# untitled.net
KiCad netlist of a schematic drawn in EAGLE
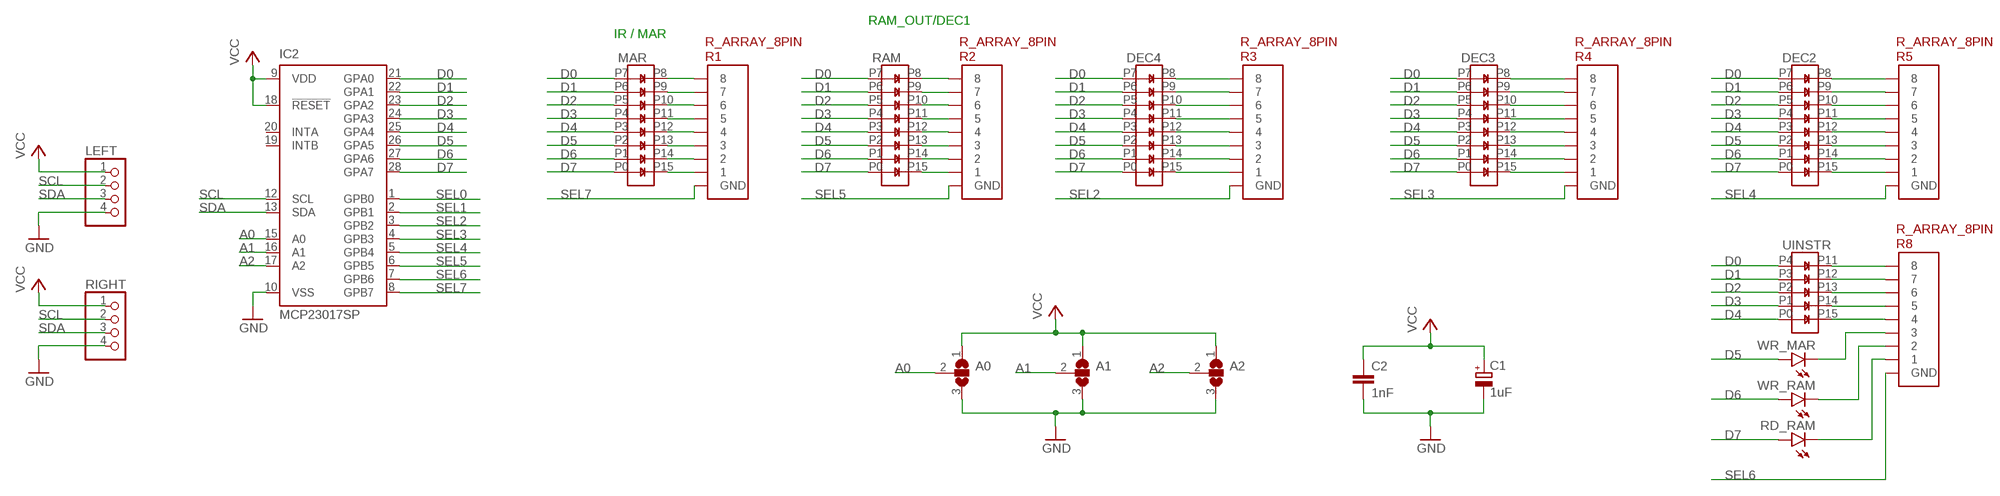
[diagram p0: schematic, sheet 1]

(export (version "E")
  (design (tool "Eeschema 10.0.6"))
  (components
    (comp (ref "A0")
      (value "SJ2W")
      (footprint "eagle-import:SJ_2")
      (libsource (lib "eagle-import") (part "SJ2W"))
    )
    (comp (ref "A1")
      (value "SJ2W")
      (footprint "eagle-import:SJ_2")
      (libsource (lib "eagle-import") (part "SJ2W"))
    )
    (comp (ref "A2")
      (value "SJ2W")
      (footprint "eagle-import:SJ_2")
      (libsource (lib "eagle-import") (part "SJ2W"))
    )
    (comp (ref "C1")
      (value "1uF")
      (footprint "eagle-import:E2,5-6")
      (libsource (lib "eagle-import") (part "CPOL-EUE2.5-6"))
    )
    (comp (ref "C2")
      (value "1nF")
      (footprint "eagle-import:C2.5-2")
      (libsource (lib "eagle-import") (part "C2.5/2"))
    )
    (comp (ref "DEC2")
      (value "LB8")
      (footprint "eagle-import:LB8")
      (libsource (lib "eagle-import") (part "LB8"))
    )
    (comp (ref "DEC3")
      (value "LB8")
      (footprint "eagle-import:LB8")
      (libsource (lib "eagle-import") (part "LB8"))
    )
    (comp (ref "DEC4")
      (value "LB8")
      (footprint "eagle-import:LB8")
      (libsource (lib "eagle-import") (part "LB8"))
    )
    (comp (ref "IC2")
      (value "MCP23017SP")
      (footprint "eagle-import:DIL28-3")
      (fields (field (name "MF") "MICROCHIP") (field (name "MPN") "MCP23017-E/SP"))
      (libsource (lib "eagle-import") (part "MCP23017SP"))
    )
    (comp (ref "LEFT")
      (value "PINHD-1X4")
      (footprint "eagle-import:1X04")
      (libsource (lib "eagle-import") (part "PINHD-1X4"))
    )
    (comp (ref "MAR")
      (value "LB8")
      (footprint "eagle-import:LB8")
      (libsource (lib "eagle-import") (part "LB8"))
    )
    (comp (ref "R1")
      (value "R_ARRAY_8PIN")
      (footprint "eagle-import:R_ARRAY_8PIN")
      (libsource (lib "eagle-import") (part "R_ARRAY_8PIN"))
    )
    (comp (ref "R2")
      (value "R_ARRAY_8PIN")
      (footprint "eagle-import:R_ARRAY_8PIN")
      (libsource (lib "eagle-import") (part "R_ARRAY_8PIN"))
    )
    (comp (ref "R3")
      (value "R_ARRAY_8PIN")
      (footprint "eagle-import:R_ARRAY_8PIN")
      (libsource (lib "eagle-import") (part "R_ARRAY_8PIN"))
    )
    (comp (ref "R4")
      (value "R_ARRAY_8PIN")
      (footprint "eagle-import:R_ARRAY_8PIN")
      (libsource (lib "eagle-import") (part "R_ARRAY_8PIN"))
    )
    (comp (ref "R5")
      (value "R_ARRAY_8PIN")
      (footprint "eagle-import:R_ARRAY_8PIN")
      (libsource (lib "eagle-import") (part "R_ARRAY_8PIN"))
    )
    (comp (ref "R8")
      (value "R_ARRAY_8PIN")
      (footprint "eagle-import:R_ARRAY_8PIN")
      (libsource (lib "eagle-import") (part "R_ARRAY_8PIN"))
    )
    (comp (ref "RAM")
      (value "LB8")
      (footprint "eagle-import:LB8")
      (libsource (lib "eagle-import") (part "LB8"))
    )
    (comp (ref "RD_RAM")
      (value "LED3MM")
      (footprint "eagle-import:LED3MM")
      (libsource (lib "eagle-import") (part "LED3MM"))
    )
    (comp (ref "RIGHT")
      (value "PINHD-1X4")
      (footprint "eagle-import:1X04")
      (libsource (lib "eagle-import") (part "PINHD-1X4"))
    )
    (comp (ref "UINSTR")
      (value "LB5")
      (footprint "eagle-import:LB5")
      (libsource (lib "eagle-import") (part "LB5"))
    )
    (comp (ref "WR_MAR")
      (value "LED3MM")
      (footprint "eagle-import:LED3MM")
      (libsource (lib "eagle-import") (part "LED3MM"))
    )
    (comp (ref "WR_RAM")
      (value "LED3MM")
      (footprint "eagle-import:LED3MM")
      (libsource (lib "eagle-import") (part "LED3MM"))
    )
  )
  (nets
    (net (code "1") (name "/A0") (class "Default")
      (node (ref "A0") (pin "2") (pinfunction "2_2") (pintype "passive"))
      (node (ref "IC2") (pin "15") (pinfunction "A0_15") (pintype "input"))
    )
    (net (code "2") (name "/A1") (class "Default")
      (node (ref "A1") (pin "2") (pinfunction "2_2") (pintype "passive"))
      (node (ref "IC2") (pin "16") (pinfunction "A1_16") (pintype "input"))
    )
    (net (code "3") (name "/A2") (class "Default")
      (node (ref "A2") (pin "2") (pinfunction "2_2") (pintype "passive"))
      (node (ref "IC2") (pin "17") (pinfunction "A2_17") (pintype "input"))
    )
    (net (code "4") (name "/D0") (class "Default")
      (node (ref "DEC2") (pin "P7") (pinfunction "P7_P7") (pintype "bidirectional"))
      (node (ref "DEC3") (pin "P7") (pinfunction "P7_P7") (pintype "bidirectional"))
      (node (ref "DEC4") (pin "P7") (pinfunction "P7_P7") (pintype "bidirectional"))
      (node (ref "IC2") (pin "21") (pinfunction "GPA0_21") (pintype "bidirectional"))
      (node (ref "MAR") (pin "P7") (pinfunction "P7_P7") (pintype "bidirectional"))
      (node (ref "RAM") (pin "P7") (pinfunction "P7_P7") (pintype "bidirectional"))
      (node (ref "UINSTR") (pin "P4") (pinfunction "P4_P4") (pintype "bidirectional"))
    )
    (net (code "5") (name "/D1") (class "Default")
      (node (ref "DEC2") (pin "P6") (pinfunction "P6_P6") (pintype "bidirectional"))
      (node (ref "DEC3") (pin "P6") (pinfunction "P6_P6") (pintype "bidirectional"))
      (node (ref "DEC4") (pin "P6") (pinfunction "P6_P6") (pintype "bidirectional"))
      (node (ref "IC2") (pin "22") (pinfunction "GPA1_22") (pintype "bidirectional"))
      (node (ref "MAR") (pin "P6") (pinfunction "P6_P6") (pintype "bidirectional"))
      (node (ref "RAM") (pin "P6") (pinfunction "P6_P6") (pintype "bidirectional"))
      (node (ref "UINSTR") (pin "P3") (pinfunction "P3_P3") (pintype "bidirectional"))
    )
    (net (code "6") (name "/D2") (class "Default")
      (node (ref "DEC2") (pin "P5") (pinfunction "P5_P5") (pintype "bidirectional"))
      (node (ref "DEC3") (pin "P5") (pinfunction "P5_P5") (pintype "bidirectional"))
      (node (ref "DEC4") (pin "P5") (pinfunction "P5_P5") (pintype "bidirectional"))
      (node (ref "IC2") (pin "23") (pinfunction "GPA2_23") (pintype "bidirectional"))
      (node (ref "MAR") (pin "P5") (pinfunction "P5_P5") (pintype "bidirectional"))
      (node (ref "RAM") (pin "P5") (pinfunction "P5_P5") (pintype "bidirectional"))
      (node (ref "UINSTR") (pin "P2") (pinfunction "P2_P2") (pintype "bidirectional"))
    )
    (net (code "7") (name "/D3") (class "Default")
      (node (ref "DEC2") (pin "P4") (pinfunction "P4_P4") (pintype "bidirectional"))
      (node (ref "DEC3") (pin "P4") (pinfunction "P4_P4") (pintype "bidirectional"))
      (node (ref "DEC4") (pin "P4") (pinfunction "P4_P4") (pintype "bidirectional"))
      (node (ref "IC2") (pin "24") (pinfunction "GPA3_24") (pintype "bidirectional"))
      (node (ref "MAR") (pin "P4") (pinfunction "P4_P4") (pintype "bidirectional"))
      (node (ref "RAM") (pin "P4") (pinfunction "P4_P4") (pintype "bidirectional"))
      (node (ref "UINSTR") (pin "P1") (pinfunction "P1_P1") (pintype "bidirectional"))
    )
    (net (code "8") (name "/D4") (class "Default")
      (node (ref "DEC2") (pin "P3") (pinfunction "P3_P3") (pintype "bidirectional"))
      (node (ref "DEC3") (pin "P3") (pinfunction "P3_P3") (pintype "bidirectional"))
      (node (ref "DEC4") (pin "P3") (pinfunction "P3_P3") (pintype "bidirectional"))
      (node (ref "IC2") (pin "25") (pinfunction "GPA4_25") (pintype "bidirectional"))
      (node (ref "MAR") (pin "P3") (pinfunction "P3_P3") (pintype "bidirectional"))
      (node (ref "RAM") (pin "P3") (pinfunction "P3_P3") (pintype "bidirectional"))
      (node (ref "UINSTR") (pin "P0") (pinfunction "P0_P0") (pintype "bidirectional"))
    )
    (net (code "9") (name "/D5") (class "Default")
      (node (ref "DEC2") (pin "P2") (pinfunction "P2_P2") (pintype "bidirectional"))
      (node (ref "DEC3") (pin "P2") (pinfunction "P2_P2") (pintype "bidirectional"))
      (node (ref "DEC4") (pin "P2") (pinfunction "P2_P2") (pintype "bidirectional"))
      (node (ref "IC2") (pin "26") (pinfunction "GPA5_26") (pintype "bidirectional"))
      (node (ref "MAR") (pin "P2") (pinfunction "P2_P2") (pintype "bidirectional"))
      (node (ref "RAM") (pin "P2") (pinfunction "P2_P2") (pintype "bidirectional"))
      (node (ref "WR_MAR") (pin "A") (pinfunction "A_A") (pintype "passive"))
    )
    (net (code "10") (name "/D6") (class "Default")
      (node (ref "DEC2") (pin "P1") (pinfunction "P1_P1") (pintype "bidirectional"))
      (node (ref "DEC3") (pin "P1") (pinfunction "P1_P1") (pintype "bidirectional"))
      (node (ref "DEC4") (pin "P1") (pinfunction "P1_P1") (pintype "bidirectional"))
      (node (ref "IC2") (pin "27") (pinfunction "GPA6_27") (pintype "bidirectional"))
      (node (ref "MAR") (pin "P1") (pinfunction "P1_P1") (pintype "bidirectional"))
      (node (ref "RAM") (pin "P1") (pinfunction "P1_P1") (pintype "bidirectional"))
      (node (ref "WR_RAM") (pin "A") (pinfunction "A_A") (pintype "passive"))
    )
    (net (code "11") (name "/D7") (class "Default")
      (node (ref "DEC2") (pin "P0") (pinfunction "P0_P0") (pintype "bidirectional"))
      (node (ref "DEC3") (pin "P0") (pinfunction "P0_P0") (pintype "bidirectional"))
      (node (ref "DEC4") (pin "P0") (pinfunction "P0_P0") (pintype "bidirectional"))
      (node (ref "IC2") (pin "28") (pinfunction "GPA7_28") (pintype "bidirectional"))
      (node (ref "MAR") (pin "P0") (pinfunction "P0_P0") (pintype "bidirectional"))
      (node (ref "RAM") (pin "P0") (pinfunction "P0_P0") (pintype "bidirectional"))
      (node (ref "RD_RAM") (pin "A") (pinfunction "A_A") (pintype "passive"))
    )
    (net (code "12") (name "/SCL") (class "Default")
      (node (ref "IC2") (pin "12") (pinfunction "SCL_12") (pintype "input"))
      (node (ref "LEFT") (pin "2") (pinfunction "2_2") (pintype "passive"))
      (node (ref "RIGHT") (pin "2") (pinfunction "2_2") (pintype "passive"))
    )
    (net (code "13") (name "/SDA") (class "Default")
      (node (ref "IC2") (pin "13") (pinfunction "SDA_13") (pintype "bidirectional"))
      (node (ref "LEFT") (pin "3") (pinfunction "3_3") (pintype "passive"))
      (node (ref "RIGHT") (pin "3") (pinfunction "3_3") (pintype "passive"))
    )
    (net (code "14") (name "/SEL0") (class "Default")
      (node (ref "IC2") (pin "1") (pinfunction "GPB0_1") (pintype "bidirectional"))
    )
    (net (code "15") (name "/SEL1") (class "Default")
      (node (ref "IC2") (pin "2") (pinfunction "GPB1_2") (pintype "bidirectional"))
    )
    (net (code "16") (name "/SEL2") (class "Default")
      (node (ref "IC2") (pin "3") (pinfunction "GPB2_3") (pintype "bidirectional"))
      (node (ref "R3") (pin "GND") (pinfunction "GND_GND") (pintype "bidirectional"))
    )
    (net (code "17") (name "/SEL3") (class "Default")
      (node (ref "IC2") (pin "4") (pinfunction "GPB3_4") (pintype "bidirectional"))
      (node (ref "R4") (pin "GND") (pinfunction "GND_GND") (pintype "bidirectional"))
    )
    (net (code "18") (name "/SEL4") (class "Default")
      (node (ref "IC2") (pin "5") (pinfunction "GPB4_5") (pintype "bidirectional"))
      (node (ref "R5") (pin "GND") (pinfunction "GND_GND") (pintype "bidirectional"))
    )
    (net (code "19") (name "/SEL5") (class "Default")
      (node (ref "IC2") (pin "6") (pinfunction "GPB5_6") (pintype "bidirectional"))
      (node (ref "R2") (pin "GND") (pinfunction "GND_GND") (pintype "bidirectional"))
    )
    (net (code "20") (name "/SEL6") (class "Default")
      (node (ref "IC2") (pin "7") (pinfunction "GPB6_7") (pintype "bidirectional"))
      (node (ref "R8") (pin "GND") (pinfunction "GND_GND") (pintype "bidirectional"))
    )
    (net (code "21") (name "/SEL7") (class "Default")
      (node (ref "IC2") (pin "8") (pinfunction "GPB7_8") (pintype "bidirectional"))
      (node (ref "R1") (pin "GND") (pinfunction "GND_GND") (pintype "bidirectional"))
    )
    (net (code "22") (name "GND") (class "Default")
      (node (ref "A0") (pin "3") (pinfunction "3_3") (pintype "passive"))
      (node (ref "A1") (pin "3") (pinfunction "3_3") (pintype "passive"))
      (node (ref "A2") (pin "3") (pinfunction "3_3") (pintype "passive"))
      (node (ref "C1") (pin "-") (pinfunction "-_-") (pintype "passive"))
      (node (ref "C2") (pin "2") (pinfunction "2_2") (pintype "passive"))
      (node (ref "IC2") (pin "10") (pinfunction "VSS_10") (pintype "power_in"))
      (node (ref "LEFT") (pin "4") (pinfunction "4_4") (pintype "passive"))
      (node (ref "RIGHT") (pin "4") (pinfunction "4_4") (pintype "passive"))
    )
    (net (code "23") (name "Net-(DEC2-PadP8)") (class "Default")
      (node (ref "DEC2") (pin "P8") (pinfunction "P8_P8") (pintype "bidirectional"))
      (node (ref "R5") (pin "8") (pinfunction "8_8") (pintype "bidirectional"))
    )
    (net (code "24") (name "Net-(DEC2-PadP9)") (class "Default")
      (node (ref "DEC2") (pin "P9") (pinfunction "P9_P9") (pintype "bidirectional"))
      (node (ref "R5") (pin "7") (pinfunction "7_7") (pintype "bidirectional"))
    )
    (net (code "25") (name "Net-(DEC2-PadP10)") (class "Default")
      (node (ref "DEC2") (pin "P10") (pinfunction "P10_P10") (pintype "bidirectional"))
      (node (ref "R5") (pin "6") (pinfunction "6_6") (pintype "bidirectional"))
    )
    (net (code "26") (name "Net-(DEC2-PadP11)") (class "Default")
      (node (ref "DEC2") (pin "P11") (pinfunction "P11_P11") (pintype "bidirectional"))
      (node (ref "R5") (pin "5") (pinfunction "5_5") (pintype "bidirectional"))
    )
    (net (code "27") (name "Net-(DEC2-PadP12)") (class "Default")
      (node (ref "DEC2") (pin "P12") (pinfunction "P12_P12") (pintype "bidirectional"))
      (node (ref "R5") (pin "4") (pinfunction "4_4") (pintype "bidirectional"))
    )
    (net (code "28") (name "Net-(DEC2-PadP13)") (class "Default")
      (node (ref "DEC2") (pin "P13") (pinfunction "P13_P13") (pintype "bidirectional"))
      (node (ref "R5") (pin "3") (pinfunction "3_3") (pintype "bidirectional"))
    )
    (net (code "29") (name "Net-(DEC2-PadP14)") (class "Default")
      (node (ref "DEC2") (pin "P14") (pinfunction "P14_P14") (pintype "bidirectional"))
      (node (ref "R5") (pin "2") (pinfunction "2_2") (pintype "bidirectional"))
    )
    (net (code "30") (name "Net-(DEC2-PadP15)") (class "Default")
      (node (ref "DEC2") (pin "P15") (pinfunction "P15_P15") (pintype "bidirectional"))
      (node (ref "R5") (pin "1") (pinfunction "1_1") (pintype "bidirectional"))
    )
    (net (code "31") (name "Net-(DEC3-PadP8)") (class "Default")
      (node (ref "DEC3") (pin "P8") (pinfunction "P8_P8") (pintype "bidirectional"))
      (node (ref "R4") (pin "8") (pinfunction "8_8") (pintype "bidirectional"))
    )
    (net (code "32") (name "Net-(DEC3-PadP9)") (class "Default")
      (node (ref "DEC3") (pin "P9") (pinfunction "P9_P9") (pintype "bidirectional"))
      (node (ref "R4") (pin "7") (pinfunction "7_7") (pintype "bidirectional"))
    )
    (net (code "33") (name "Net-(DEC3-PadP10)") (class "Default")
      (node (ref "DEC3") (pin "P10") (pinfunction "P10_P10") (pintype "bidirectional"))
      (node (ref "R4") (pin "6") (pinfunction "6_6") (pintype "bidirectional"))
    )
    (net (code "34") (name "Net-(DEC3-PadP11)") (class "Default")
      (node (ref "DEC3") (pin "P11") (pinfunction "P11_P11") (pintype "bidirectional"))
      (node (ref "R4") (pin "5") (pinfunction "5_5") (pintype "bidirectional"))
    )
    (net (code "35") (name "Net-(DEC3-PadP12)") (class "Default")
      (node (ref "DEC3") (pin "P12") (pinfunction "P12_P12") (pintype "bidirectional"))
      (node (ref "R4") (pin "4") (pinfunction "4_4") (pintype "bidirectional"))
    )
    (net (code "36") (name "Net-(DEC3-PadP13)") (class "Default")
      (node (ref "DEC3") (pin "P13") (pinfunction "P13_P13") (pintype "bidirectional"))
      (node (ref "R4") (pin "3") (pinfunction "3_3") (pintype "bidirectional"))
    )
    (net (code "37") (name "Net-(DEC3-PadP14)") (class "Default")
      (node (ref "DEC3") (pin "P14") (pinfunction "P14_P14") (pintype "bidirectional"))
      (node (ref "R4") (pin "2") (pinfunction "2_2") (pintype "bidirectional"))
    )
    (net (code "38") (name "Net-(DEC3-PadP15)") (class "Default")
      (node (ref "DEC3") (pin "P15") (pinfunction "P15_P15") (pintype "bidirectional"))
      (node (ref "R4") (pin "1") (pinfunction "1_1") (pintype "bidirectional"))
    )
    (net (code "39") (name "Net-(DEC4-PadP8)") (class "Default")
      (node (ref "DEC4") (pin "P8") (pinfunction "P8_P8") (pintype "bidirectional"))
      (node (ref "R3") (pin "8") (pinfunction "8_8") (pintype "bidirectional"))
    )
    (net (code "40") (name "Net-(DEC4-PadP9)") (class "Default")
      (node (ref "DEC4") (pin "P9") (pinfunction "P9_P9") (pintype "bidirectional"))
      (node (ref "R3") (pin "7") (pinfunction "7_7") (pintype "bidirectional"))
    )
    (net (code "41") (name "Net-(DEC4-PadP10)") (class "Default")
      (node (ref "DEC4") (pin "P10") (pinfunction "P10_P10") (pintype "bidirectional"))
      (node (ref "R3") (pin "6") (pinfunction "6_6") (pintype "bidirectional"))
    )
    (net (code "42") (name "Net-(DEC4-PadP11)") (class "Default")
      (node (ref "DEC4") (pin "P11") (pinfunction "P11_P11") (pintype "bidirectional"))
      (node (ref "R3") (pin "5") (pinfunction "5_5") (pintype "bidirectional"))
    )
    (net (code "43") (name "Net-(DEC4-PadP12)") (class "Default")
      (node (ref "DEC4") (pin "P12") (pinfunction "P12_P12") (pintype "bidirectional"))
      (node (ref "R3") (pin "4") (pinfunction "4_4") (pintype "bidirectional"))
    )
    (net (code "44") (name "Net-(DEC4-PadP13)") (class "Default")
      (node (ref "DEC4") (pin "P13") (pinfunction "P13_P13") (pintype "bidirectional"))
      (node (ref "R3") (pin "3") (pinfunction "3_3") (pintype "bidirectional"))
    )
    (net (code "45") (name "Net-(DEC4-PadP14)") (class "Default")
      (node (ref "DEC4") (pin "P14") (pinfunction "P14_P14") (pintype "bidirectional"))
      (node (ref "R3") (pin "2") (pinfunction "2_2") (pintype "bidirectional"))
    )
    (net (code "46") (name "Net-(DEC4-PadP15)") (class "Default")
      (node (ref "DEC4") (pin "P15") (pinfunction "P15_P15") (pintype "bidirectional"))
      (node (ref "R3") (pin "1") (pinfunction "1_1") (pintype "bidirectional"))
    )
    (net (code "47") (name "Net-(MAR-PadP8)") (class "Default")
      (node (ref "MAR") (pin "P8") (pinfunction "P8_P8") (pintype "bidirectional"))
      (node (ref "R1") (pin "8") (pinfunction "8_8") (pintype "bidirectional"))
    )
    (net (code "48") (name "Net-(MAR-PadP9)") (class "Default")
      (node (ref "MAR") (pin "P9") (pinfunction "P9_P9") (pintype "bidirectional"))
      (node (ref "R1") (pin "7") (pinfunction "7_7") (pintype "bidirectional"))
    )
    (net (code "49") (name "Net-(MAR-PadP10)") (class "Default")
      (node (ref "MAR") (pin "P10") (pinfunction "P10_P10") (pintype "bidirectional"))
      (node (ref "R1") (pin "6") (pinfunction "6_6") (pintype "bidirectional"))
    )
    (net (code "50") (name "Net-(MAR-PadP11)") (class "Default")
      (node (ref "MAR") (pin "P11") (pinfunction "P11_P11") (pintype "bidirectional"))
      (node (ref "R1") (pin "5") (pinfunction "5_5") (pintype "bidirectional"))
    )
    (net (code "51") (name "Net-(MAR-PadP12)") (class "Default")
      (node (ref "MAR") (pin "P12") (pinfunction "P12_P12") (pintype "bidirectional"))
      (node (ref "R1") (pin "4") (pinfunction "4_4") (pintype "bidirectional"))
    )
    (net (code "52") (name "Net-(MAR-PadP13)") (class "Default")
      (node (ref "MAR") (pin "P13") (pinfunction "P13_P13") (pintype "bidirectional"))
      (node (ref "R1") (pin "3") (pinfunction "3_3") (pintype "bidirectional"))
    )
    (net (code "53") (name "Net-(MAR-PadP14)") (class "Default")
      (node (ref "MAR") (pin "P14") (pinfunction "P14_P14") (pintype "bidirectional"))
      (node (ref "R1") (pin "2") (pinfunction "2_2") (pintype "bidirectional"))
    )
    (net (code "54") (name "Net-(MAR-PadP15)") (class "Default")
      (node (ref "MAR") (pin "P15") (pinfunction "P15_P15") (pintype "bidirectional"))
      (node (ref "R1") (pin "1") (pinfunction "1_1") (pintype "bidirectional"))
    )
    (net (code "55") (name "Net-(R2-Pad1)") (class "Default")
      (node (ref "R2") (pin "1") (pinfunction "1_1") (pintype "bidirectional"))
      (node (ref "RAM") (pin "P15") (pinfunction "P15_P15") (pintype "bidirectional"))
    )
    (net (code "56") (name "Net-(R2-Pad2)") (class "Default")
      (node (ref "R2") (pin "2") (pinfunction "2_2") (pintype "bidirectional"))
      (node (ref "RAM") (pin "P14") (pinfunction "P14_P14") (pintype "bidirectional"))
    )
    (net (code "57") (name "Net-(R2-Pad3)") (class "Default")
      (node (ref "R2") (pin "3") (pinfunction "3_3") (pintype "bidirectional"))
      (node (ref "RAM") (pin "P13") (pinfunction "P13_P13") (pintype "bidirectional"))
    )
    (net (code "58") (name "Net-(R2-Pad4)") (class "Default")
      (node (ref "R2") (pin "4") (pinfunction "4_4") (pintype "bidirectional"))
      (node (ref "RAM") (pin "P12") (pinfunction "P12_P12") (pintype "bidirectional"))
    )
    (net (code "59") (name "Net-(R2-Pad5)") (class "Default")
      (node (ref "R2") (pin "5") (pinfunction "5_5") (pintype "bidirectional"))
      (node (ref "RAM") (pin "P11") (pinfunction "P11_P11") (pintype "bidirectional"))
    )
    (net (code "60") (name "Net-(R2-Pad6)") (class "Default")
      (node (ref "R2") (pin "6") (pinfunction "6_6") (pintype "bidirectional"))
      (node (ref "RAM") (pin "P10") (pinfunction "P10_P10") (pintype "bidirectional"))
    )
    (net (code "61") (name "Net-(R2-Pad7)") (class "Default")
      (node (ref "R2") (pin "7") (pinfunction "7_7") (pintype "bidirectional"))
      (node (ref "RAM") (pin "P9") (pinfunction "P9_P9") (pintype "bidirectional"))
    )
    (net (code "62") (name "Net-(R2-Pad8)") (class "Default")
      (node (ref "R2") (pin "8") (pinfunction "8_8") (pintype "bidirectional"))
      (node (ref "RAM") (pin "P8") (pinfunction "P8_P8") (pintype "bidirectional"))
    )
    (net (code "63") (name "Net-(R8-Pad4)") (class "Default")
      (node (ref "R8") (pin "4") (pinfunction "4_4") (pintype "bidirectional"))
      (node (ref "UINSTR") (pin "P15") (pinfunction "P15_P15") (pintype "bidirectional"))
    )
    (net (code "64") (name "Net-(R8-Pad5)") (class "Default")
      (node (ref "R8") (pin "5") (pinfunction "5_5") (pintype "bidirectional"))
      (node (ref "UINSTR") (pin "P14") (pinfunction "P14_P14") (pintype "bidirectional"))
    )
    (net (code "65") (name "Net-(R8-Pad6)") (class "Default")
      (node (ref "R8") (pin "6") (pinfunction "6_6") (pintype "bidirectional"))
      (node (ref "UINSTR") (pin "P13") (pinfunction "P13_P13") (pintype "bidirectional"))
    )
    (net (code "66") (name "Net-(R8-Pad7)") (class "Default")
      (node (ref "R8") (pin "7") (pinfunction "7_7") (pintype "bidirectional"))
      (node (ref "UINSTR") (pin "P12") (pinfunction "P12_P12") (pintype "bidirectional"))
    )
    (net (code "67") (name "Net-(R8-Pad8)") (class "Default")
      (node (ref "R8") (pin "8") (pinfunction "8_8") (pintype "bidirectional"))
      (node (ref "UINSTR") (pin "P11") (pinfunction "P11_P11") (pintype "bidirectional"))
    )
    (net (code "68") (name "Net-(RD_RAM-C)") (class "Default")
      (node (ref "R8") (pin "1") (pinfunction "1_1") (pintype "bidirectional"))
      (node (ref "RD_RAM") (pin "K") (pinfunction "C_K") (pintype "passive"))
    )
    (net (code "69") (name "Net-(WR_MAR-C)") (class "Default")
      (node (ref "R8") (pin "3") (pinfunction "3_3") (pintype "bidirectional"))
      (node (ref "WR_MAR") (pin "K") (pinfunction "C_K") (pintype "passive"))
    )
    (net (code "70") (name "Net-(WR_RAM-C)") (class "Default")
      (node (ref "R8") (pin "2") (pinfunction "2_2") (pintype "bidirectional"))
      (node (ref "WR_RAM") (pin "K") (pinfunction "C_K") (pintype "passive"))
    )
    (net (code "71") (name "VCC") (class "Default")
      (node (ref "A0") (pin "1") (pinfunction "1_1") (pintype "passive"))
      (node (ref "A1") (pin "1") (pinfunction "1_1") (pintype "passive"))
      (node (ref "A2") (pin "1") (pinfunction "1_1") (pintype "passive"))
      (node (ref "C1") (pin "+") (pinfunction "+_+") (pintype "passive"))
      (node (ref "C2") (pin "1") (pinfunction "1_1") (pintype "passive"))
      (node (ref "IC2") (pin "18") (pinfunction "~{RESET}_18") (pintype "input"))
      (node (ref "IC2") (pin "9") (pinfunction "VDD_9") (pintype "power_in"))
      (node (ref "LEFT") (pin "1") (pinfunction "1_1") (pintype "passive"))
      (node (ref "RIGHT") (pin "1") (pinfunction "1_1") (pintype "passive"))
    )
    (net (code "72") (name "unconnected-(IC2-INTA-Pad20)") (class "Default")
      (node (ref "IC2") (pin "20") (pinfunction "INTA_20") (pintype "output"))
    )
    (net (code "73") (name "unconnected-(IC2-INTB-Pad19)") (class "Default")
      (node (ref "IC2") (pin "19") (pinfunction "INTB_19") (pintype "output"))
    )
  )
)
